# nanopi-black2-shield.net
KiCad netlist of a schematic drawn in EAGLE
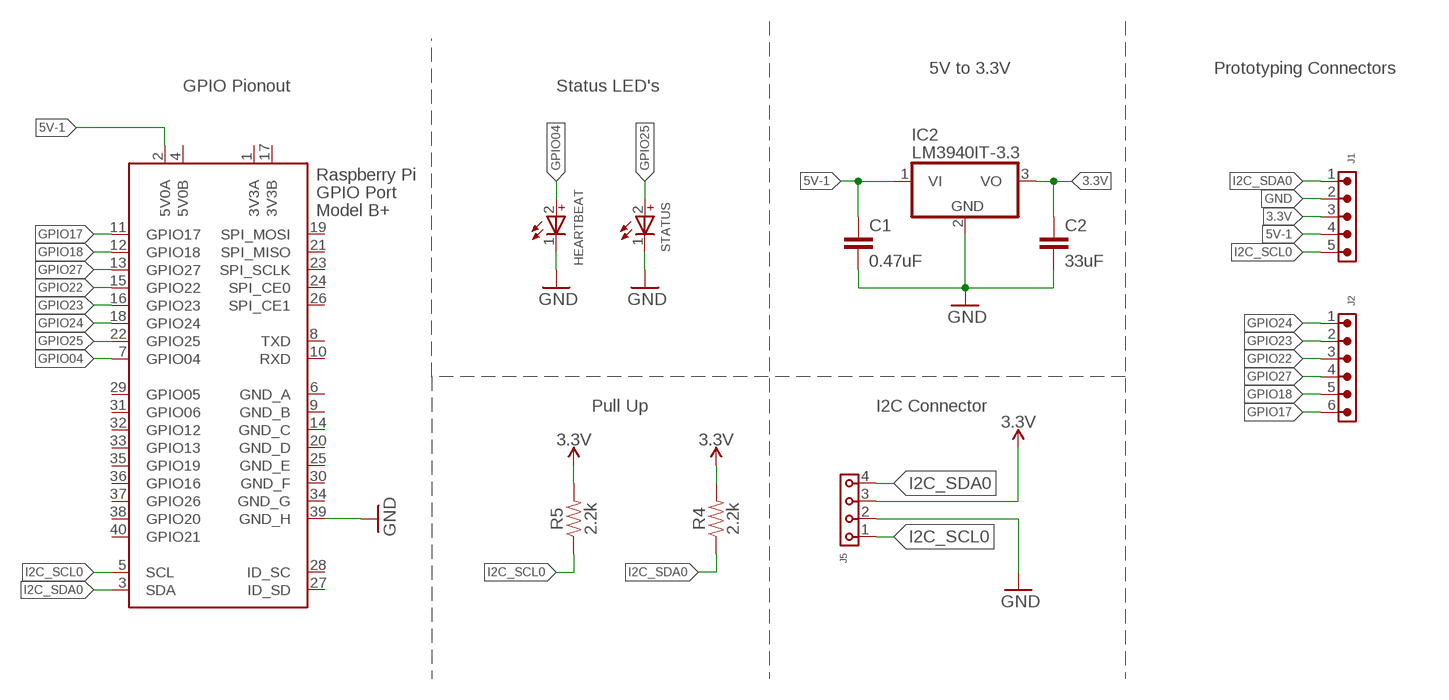
[diagram p0: schematic, sheet 1]

(export (version "E")
  (design (tool "Eeschema 10.0.6"))
  (components
    (comp (ref "C1")
      (value "0.47uF")
      (footprint "eagle-import:0603")
      (libsource (lib "eagle-import") (part "1.0UF-0603-16V-10%"))
    )
    (comp (ref "C2")
      (value "33uF")
      (footprint "eagle-import:C0805")
      (libsource (lib "eagle-import") (part "C-EUC0805"))
    )
    (comp (ref "HEARTBEAT")
      (value "WL-SMSW_0603_REC_155060RS75300")
      (footprint "eagle-import:WL-SMSW_0603_REC")
      (libsource (lib "eagle-import") (part "WL-SMSW_0603_REC_155060RS75300"))
    )
    (comp (ref "IC2")
      (value "LM3940IT-3.3")
      (footprint "eagle-import:TO220H")
      (libsource (lib "eagle-import") (part "78T18"))
    )
    (comp (ref "J1")
      (value "6130XX11121_61300511121")
      (footprint "eagle-import:61300511121")
      (libsource (lib "eagle-import") (part "6130XX11121_61300511121"))
    )
    (comp (ref "J2")
      (value "6130XX11121_61300611121")
      (footprint "eagle-import:61300611121")
      (libsource (lib "eagle-import") (part "6130XX11121_61300611121"))
    )
    (comp (ref "J5")
      (value "6130XX11821_61300411821")
      (footprint "eagle-import:61300411821")
      (libsource (lib "eagle-import") (part "6130XX11821_61300411821"))
    )
    (comp (ref "R4")
      (value "2.2k")
      (footprint "eagle-import:0603")
      (libsource (lib "eagle-import") (part "2.2KOHM-0603-1/10W-1%"))
    )
    (comp (ref "R5")
      (value "2.2k")
      (footprint "eagle-import:0603")
      (libsource (lib "eagle-import") (part "2.2KOHM-0603-1/10W-1%"))
    )
    (comp (ref "STATUS")
      (value "WL-SMSW_0603_REC_155060GS75300")
      (footprint "eagle-import:WL-SMSW_0603_REC")
      (libsource (lib "eagle-import") (part "WL-SMSW_0603_REC_155060GS75300"))
    )
    (comp (ref "X1")
      (value "RASPI_BOARD_B+#_HDC")
      (footprint "eagle-import:RASPI_BOARD_B+HAT_DF_CF")
      (libsource (lib "eagle-import") (part "RASPI_BOARD_B+#_HDC"))
    )
  )
  (nets
    (net (code "1") (name "/3V3A") (class "Default")
      (node (ref "X1") (pin "1") (pinfunction "3V3A_1") (pintype "power_in"))
    )
    (net (code "2") (name "/3V3B") (class "Default")
      (node (ref "X1") (pin "17") (pinfunction "3V3B_17") (pintype "power_in"))
    )
    (net (code "3") (name "/5V0B") (class "Default")
      (node (ref "X1") (pin "4") (pinfunction "5V0B_4") (pintype "power_in"))
    )
    (net (code "4") (name "/GND_A") (class "Default")
      (node (ref "X1") (pin "6") (pinfunction "GND_A_6") (pintype "power_in"))
    )
    (net (code "5") (name "/GND_B") (class "Default")
      (node (ref "X1") (pin "9") (pinfunction "GND_B_9") (pintype "power_in"))
    )
    (net (code "6") (name "/GND_C") (class "Default")
      (node (ref "X1") (pin "14") (pinfunction "GND_C_14") (pintype "power_in"))
    )
    (net (code "7") (name "/GND_D") (class "Default")
      (node (ref "X1") (pin "20") (pinfunction "GND_D_20") (pintype "power_in"))
    )
    (net (code "8") (name "/GND_E") (class "Default")
      (node (ref "X1") (pin "25") (pinfunction "GND_E_25") (pintype "power_in"))
    )
    (net (code "9") (name "/GND_F") (class "Default")
      (node (ref "X1") (pin "30") (pinfunction "GND_F_30") (pintype "power_in"))
    )
    (net (code "10") (name "/GND_G") (class "Default")
      (node (ref "X1") (pin "34") (pinfunction "GND_G_34") (pintype "power_in"))
    )
    (net (code "11") (name "3.3V") (class "Default")
      (node (ref "C2") (pin "1") (pinfunction "1_1") (pintype "passive"))
      (node (ref "IC2") (pin "3") (pinfunction "VO_3") (pintype "passive"))
      (node (ref "J1") (pin "3") (pinfunction "3_3") (pintype "passive"))
      (node (ref "J5") (pin "3") (pinfunction "3_3") (pintype "passive"))
      (node (ref "R4") (pin "2") (pinfunction "2_2") (pintype "passive"))
      (node (ref "R5") (pin "2") (pinfunction "2_2") (pintype "passive"))
    )
    (net (code "12") (name "5V-1") (class "Default")
      (node (ref "C1") (pin "1") (pinfunction "1_1") (pintype "passive"))
      (node (ref "IC2") (pin "1") (pinfunction "VI_1") (pintype "input"))
      (node (ref "J1") (pin "4") (pinfunction "4_4") (pintype "passive"))
      (node (ref "X1") (pin "2") (pinfunction "5V0A_2") (pintype "power_in"))
    )
    (net (code "13") (name "GND") (class "Default")
      (node (ref "C1") (pin "2") (pinfunction "2_2") (pintype "passive"))
      (node (ref "C2") (pin "2") (pinfunction "2_2") (pintype "passive"))
      (node (ref "HEARTBEAT") (pin "1") (pinfunction "-_1") (pintype "passive"))
      (node (ref "IC2") (pin "2") (pinfunction "GND_2") (pintype "passive"))
      (node (ref "J1") (pin "2") (pinfunction "2_2") (pintype "passive"))
      (node (ref "J5") (pin "2") (pinfunction "2_2") (pintype "passive"))
      (node (ref "STATUS") (pin "1") (pinfunction "-_1") (pintype "passive"))
      (node (ref "X1") (pin "39") (pinfunction "GND_H_39") (pintype "power_in"))
    )
    (net (code "14") (name "GPIO04") (class "Default")
      (node (ref "HEARTBEAT") (pin "2") (pinfunction "+_2") (pintype "passive"))
      (node (ref "X1") (pin "7") (pinfunction "GPIO04_7") (pintype "bidirectional"))
    )
    (net (code "15") (name "GPIO17") (class "Default")
      (node (ref "J2") (pin "6") (pinfunction "6_6") (pintype "passive"))
      (node (ref "X1") (pin "11") (pinfunction "GPIO17_11") (pintype "bidirectional"))
    )
    (net (code "16") (name "GPIO18") (class "Default")
      (node (ref "J2") (pin "5") (pinfunction "5_5") (pintype "passive"))
      (node (ref "X1") (pin "12") (pinfunction "GPIO18_12") (pintype "bidirectional"))
    )
    (net (code "17") (name "GPIO22") (class "Default")
      (node (ref "J2") (pin "3") (pinfunction "3_3") (pintype "passive"))
      (node (ref "X1") (pin "15") (pinfunction "GPIO22_15") (pintype "bidirectional"))
    )
    (net (code "18") (name "GPIO23") (class "Default")
      (node (ref "J2") (pin "2") (pinfunction "2_2") (pintype "passive"))
      (node (ref "X1") (pin "16") (pinfunction "GPIO23_16") (pintype "bidirectional"))
    )
    (net (code "19") (name "GPIO24") (class "Default")
      (node (ref "J2") (pin "1") (pinfunction "1_1") (pintype "passive"))
      (node (ref "X1") (pin "18") (pinfunction "GPIO24_18") (pintype "bidirectional"))
    )
    (net (code "20") (name "GPIO25") (class "Default")
      (node (ref "STATUS") (pin "2") (pinfunction "+_2") (pintype "passive"))
      (node (ref "X1") (pin "22") (pinfunction "GPIO25_22") (pintype "bidirectional"))
    )
    (net (code "21") (name "GPIO27") (class "Default")
      (node (ref "J2") (pin "4") (pinfunction "4_4") (pintype "passive"))
      (node (ref "X1") (pin "13") (pinfunction "GPIO27_13") (pintype "bidirectional"))
    )
    (net (code "22") (name "I2C_SCL0") (class "Default")
      (node (ref "J1") (pin "5") (pinfunction "5_5") (pintype "passive"))
      (node (ref "J5") (pin "1") (pinfunction "1_1") (pintype "passive"))
      (node (ref "R5") (pin "1") (pinfunction "1_1") (pintype "passive"))
      (node (ref "X1") (pin "5") (pinfunction "SCL_5") (pintype "bidirectional"))
    )
    (net (code "23") (name "I2C_SDA0") (class "Default")
      (node (ref "J1") (pin "1") (pinfunction "1_1") (pintype "passive"))
      (node (ref "J5") (pin "4") (pinfunction "4_4") (pintype "passive"))
      (node (ref "R4") (pin "1") (pinfunction "1_1") (pintype "passive"))
      (node (ref "X1") (pin "3") (pinfunction "SDA_3") (pintype "bidirectional"))
    )
    (net (code "24") (name "unconnected-(X1-GPIO05-Pad29)") (class "Default")
      (node (ref "X1") (pin "29") (pinfunction "GPIO05_29") (pintype "no_connect"))
    )
    (net (code "25") (name "unconnected-(X1-GPIO06-Pad31)") (class "Default")
      (node (ref "X1") (pin "31") (pinfunction "GPIO06_31") (pintype "no_connect"))
    )
    (net (code "26") (name "unconnected-(X1-GPIO12-Pad32)") (class "Default")
      (node (ref "X1") (pin "32") (pinfunction "GPIO12_32") (pintype "no_connect"))
    )
    (net (code "27") (name "unconnected-(X1-GPIO13-Pad33)") (class "Default")
      (node (ref "X1") (pin "33") (pinfunction "GPIO13_33") (pintype "no_connect"))
    )
    (net (code "28") (name "unconnected-(X1-GPIO16-Pad36)") (class "Default")
      (node (ref "X1") (pin "36") (pinfunction "GPIO16_36") (pintype "no_connect"))
    )
    (net (code "29") (name "unconnected-(X1-GPIO19-Pad35)") (class "Default")
      (node (ref "X1") (pin "35") (pinfunction "GPIO19_35") (pintype "no_connect"))
    )
    (net (code "30") (name "unconnected-(X1-GPIO20-Pad38)") (class "Default")
      (node (ref "X1") (pin "38") (pinfunction "GPIO20_38") (pintype "no_connect"))
    )
    (net (code "31") (name "unconnected-(X1-GPIO21-Pad40)") (class "Default")
      (node (ref "X1") (pin "40") (pinfunction "GPIO21_40") (pintype "no_connect"))
    )
    (net (code "32") (name "unconnected-(X1-GPIO26-Pad37)") (class "Default")
      (node (ref "X1") (pin "37") (pinfunction "GPIO26_37") (pintype "no_connect"))
    )
    (net (code "33") (name "unconnected-(X1-ID_SC-Pad28)") (class "Default")
      (node (ref "X1") (pin "28") (pinfunction "ID_SC_28") (pintype "no_connect"))
    )
    (net (code "34") (name "unconnected-(X1-ID_SD-Pad27)") (class "Default")
      (node (ref "X1") (pin "27") (pinfunction "ID_SD_27") (pintype "no_connect"))
    )
    (net (code "35") (name "unconnected-(X1-RXD-Pad10)") (class "Default")
      (node (ref "X1") (pin "10") (pinfunction "RXD_10") (pintype "bidirectional"))
    )
    (net (code "36") (name "unconnected-(X1-SPI_CE0-Pad24)") (class "Default")
      (node (ref "X1") (pin "24") (pinfunction "SPI_CE0_24") (pintype "bidirectional"))
    )
    (net (code "37") (name "unconnected-(X1-SPI_CE1-Pad26)") (class "Default")
      (node (ref "X1") (pin "26") (pinfunction "SPI_CE1_26") (pintype "bidirectional"))
    )
    (net (code "38") (name "unconnected-(X1-SPI_MISO-Pad21)") (class "Default")
      (node (ref "X1") (pin "21") (pinfunction "SPI_MISO_21") (pintype "bidirectional"))
    )
    (net (code "39") (name "unconnected-(X1-SPI_MOSI-Pad19)") (class "Default")
      (node (ref "X1") (pin "19") (pinfunction "SPI_MOSI_19") (pintype "bidirectional"))
    )
    (net (code "40") (name "unconnected-(X1-SPI_SCLK-Pad23)") (class "Default")
      (node (ref "X1") (pin "23") (pinfunction "SPI_SCLK_23") (pintype "bidirectional"))
    )
    (net (code "41") (name "unconnected-(X1-TXD-Pad8)") (class "Default")
      (node (ref "X1") (pin "8") (pinfunction "TXD_8") (pintype "bidirectional"))
    )
  )
)
